# class_nrf52840v2_module.net
KiCad netlist of a schematic drawn in EAGLE
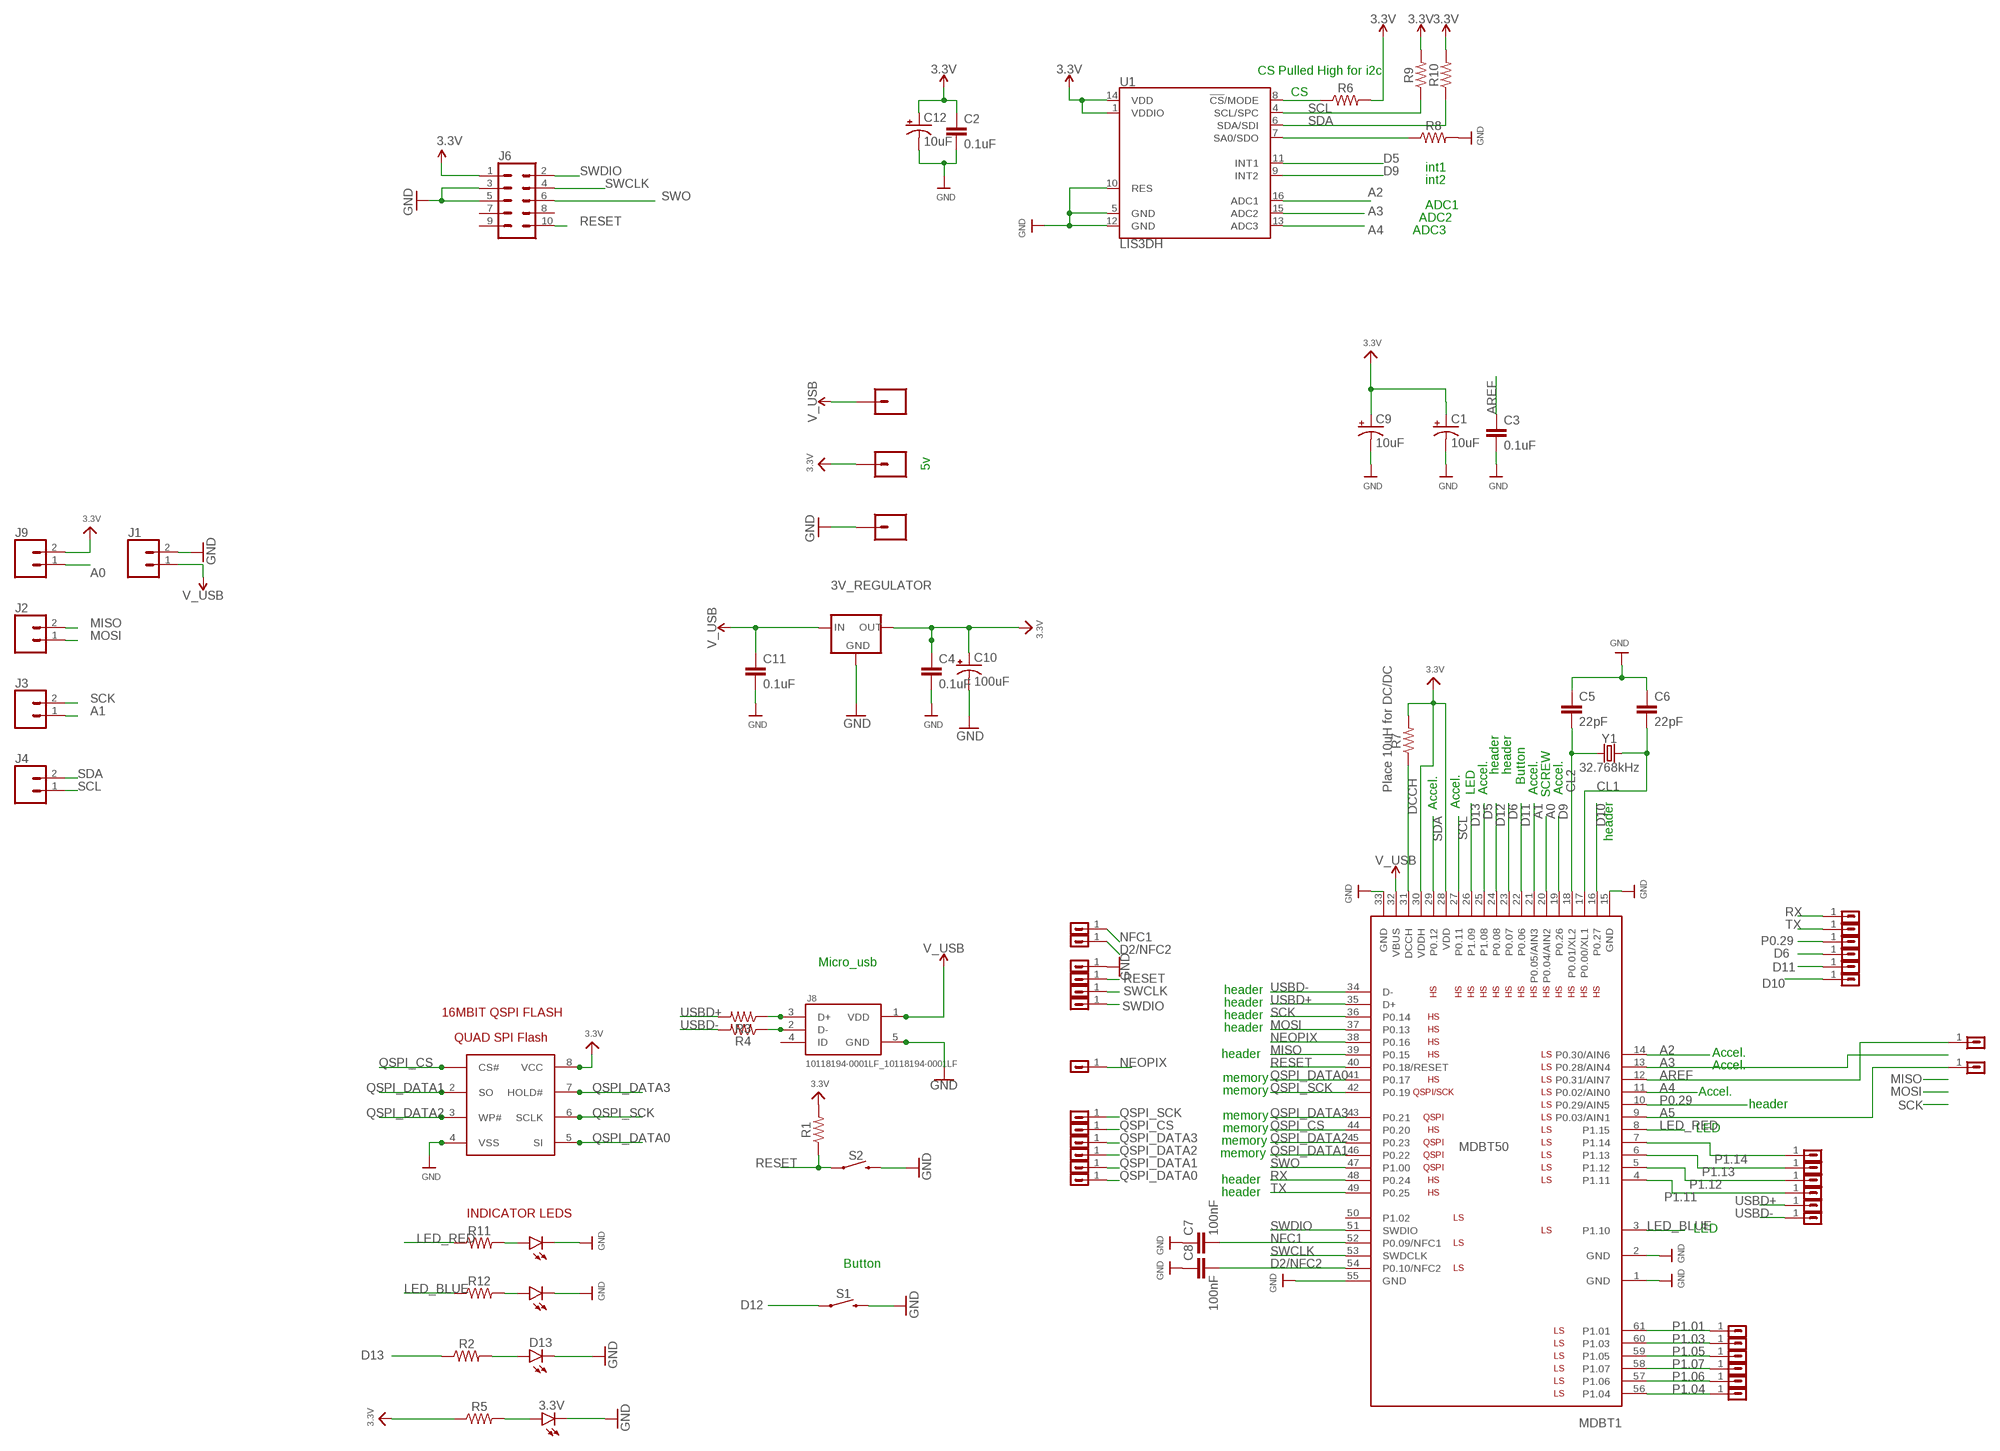
[diagram p0: schematic, sheet 1]

(export (version "E")
  (design (tool "Eeschema 10.0.6"))
  (components
    (comp (ref "3.3V")
      (value "LED5MM-KIT")
      (footprint "eagle-import:LED5MM-KIT")
      (libsource (lib "eagle-import") (part "LED5MM-KIT"))
    )
    (comp (ref "3V_REGULATOR")
      (value "LDL1117_5V_REG")
      (footprint "eagle-import:SOT223")
      (libsource (lib "eagle-import") (part "LDL1117_5V_REG"))
    )
    (comp (ref "C1")
      (value "10uF")
      (footprint "eagle-import:CPOL-RADIAL-2.5MM-5MM-KIT")
      (libsource (lib "eagle-import") (part "10UF-POLAR-RADIAL-2.5MM-KIT-25V-20%"))
    )
    (comp (ref "C2")
      (value "0.1uF")
      (footprint "eagle-import:CAP-PTH-SMALL-KIT")
      (libsource (lib "eagle-import") (part "0.1UF-KIT-EZ-50V-20%"))
    )
    (comp (ref "C3")
      (value "0.1uF")
      (footprint "eagle-import:CAP-PTH-SMALL-KIT")
      (libsource (lib "eagle-import") (part "0.1UF-KIT-EZ-50V-20%"))
    )
    (comp (ref "C4")
      (value "0.1uF")
      (footprint "eagle-import:CAP-PTH-SMALL-KIT")
      (libsource (lib "eagle-import") (part "0.1UF-KIT-EZ-50V-20%"))
    )
    (comp (ref "C5")
      (value "22pF")
      (footprint "eagle-import:CAP-PTH-SMALL-KIT")
      (libsource (lib "eagle-import") (part "0.1UF-KIT-EZ-50V-20%"))
    )
    (comp (ref "C6")
      (value "22pF")
      (footprint "eagle-import:CAP-PTH-SMALL-KIT")
      (libsource (lib "eagle-import") (part "0.1UF-KIT-EZ-50V-20%"))
    )
    (comp (ref "C7")
      (value "100nF")
      (footprint "eagle-import:0805")
      (libsource (lib "eagle-import") (part "10UF-0805-10V-10%"))
    )
    (comp (ref "C8")
      (value "100nF")
      (footprint "eagle-import:0805")
      (libsource (lib "eagle-import") (part "10UF-0805-10V-10%"))
    )
    (comp (ref "C9")
      (value "10uF")
      (footprint "eagle-import:CPOL-RADIAL-2.5MM-5MM-KIT")
      (libsource (lib "eagle-import") (part "10UF-POLAR-RADIAL-2.5MM-KIT-25V-20%"))
    )
    (comp (ref "C10")
      (value "100uF")
      (footprint "eagle-import:CPOL-RADIAL-2.5MM-6.5MM")
      (libsource (lib "eagle-import") (part "100UF-POLAR-RADIAL-2.5MM-25V-20%"))
    )
    (comp (ref "C11")
      (value "0.1uF")
      (footprint "eagle-import:CAP-PTH-SMALL-KIT")
      (libsource (lib "eagle-import") (part "0.1UF-KIT-EZ-50V-20%"))
    )
    (comp (ref "C12")
      (value "10uF")
      (footprint "eagle-import:CPOL-RADIAL-2.5MM-5MM-KIT")
      (libsource (lib "eagle-import") (part "10UF-POLAR-RADIAL-2.5MM-KIT-25V-20%"))
    )
    (comp (ref "D2")
      (value "LED5MM-KIT")
      (footprint "eagle-import:LED5MM-KIT")
      (libsource (lib "eagle-import") (part "LED5MM-KIT"))
    )
    (comp (ref "D3")
      (value "LED5MM-KIT")
      (footprint "eagle-import:LED5MM-KIT")
      (libsource (lib "eagle-import") (part "LED5MM-KIT"))
    )
    (comp (ref "D13")
      (value "LED5MM-KIT")
      (footprint "eagle-import:LED5MM-KIT")
      (libsource (lib "eagle-import") (part "LED5MM-KIT"))
    )
    (comp (ref "J1")
      (value "CONN_025MM")
      (footprint "eagle-import:SCREWTERMINAL-5MM-2")
      (libsource (lib "eagle-import") (part "CONN_025MM"))
    )
    (comp (ref "J2")
      (value "CONN_025MM")
      (footprint "eagle-import:SCREWTERMINAL-5MM-2")
      (libsource (lib "eagle-import") (part "CONN_025MM"))
    )
    (comp (ref "J3")
      (value "CONN_025MM")
      (footprint "eagle-import:SCREWTERMINAL-5MM-2")
      (libsource (lib "eagle-import") (part "CONN_025MM"))
    )
    (comp (ref "J4")
      (value "CONN_025MM")
      (footprint "eagle-import:SCREWTERMINAL-5MM-2")
      (libsource (lib "eagle-import") (part "CONN_025MM"))
    )
    (comp (ref "J5")
      (value "M01PTH")
      (footprint "eagle-import:1X01")
      (libsource (lib "eagle-import") (part "M01PTH"))
    )
    (comp (ref "J6")
      (value "CONN_05X2SHD_SMD")
      (footprint "eagle-import:2X5-SHROUDED_SMD")
      (libsource (lib "eagle-import") (part "CONN_05X2SHD_SMD"))
    )
    (comp (ref "J7")
      (value "M01PTH")
      (footprint "eagle-import:1X01")
      (libsource (lib "eagle-import") (part "M01PTH"))
    )
    (comp (ref "J8")
      (value "10118194-0001LF_10118194-0001LF")
      (footprint "eagle-import:10118194-0001LF_FRAMATOME_10118194-0001LF")
      (fields (field (name "MF") "Amphenol ICC") (field (name "MP") "10118194-0001LF"))
      (libsource (lib "eagle-import") (part "10118194-0001LF_10118194-0001LF"))
    )
    (comp (ref "J9")
      (value "CONN_025MM")
      (footprint "eagle-import:SCREWTERMINAL-5MM-2")
      (libsource (lib "eagle-import") (part "CONN_025MM"))
    )
    (comp (ref "J17")
      (value "M01PTH")
      (footprint "eagle-import:1X01")
      (libsource (lib "eagle-import") (part "M01PTH"))
    )
    (comp (ref "MDBT1")
      (value "MDBT50")
      (footprint "eagle-import:MDBT50")
      (libsource (lib "eagle-import") (part "MDBT50"))
    )
    (comp (ref "R1")
      (value "RESISTORAXIAL-0.3")
      (footprint "eagle-import:AXIAL-0.3")
      (libsource (lib "eagle-import") (part "RESISTORAXIAL-0.3"))
    )
    (comp (ref "R2")
      (value "RESISTORAXIAL-0.3")
      (footprint "eagle-import:AXIAL-0.3")
      (libsource (lib "eagle-import") (part "RESISTORAXIAL-0.3"))
    )
    (comp (ref "R3")
      (value "RESISTOR0805")
      (footprint "eagle-import:0805")
      (libsource (lib "eagle-import") (part "RESISTOR0805"))
    )
    (comp (ref "R4")
      (value "RESISTOR0805")
      (footprint "eagle-import:0805")
      (libsource (lib "eagle-import") (part "RESISTOR0805"))
    )
    (comp (ref "R5")
      (value "RESISTORAXIAL-0.3")
      (footprint "eagle-import:AXIAL-0.3")
      (libsource (lib "eagle-import") (part "RESISTORAXIAL-0.3"))
    )
    (comp (ref "R6")
      (value "RESISTOR0805")
      (footprint "eagle-import:0805")
      (libsource (lib "eagle-import") (part "RESISTOR0805"))
    )
    (comp (ref "R7")
      (value "RESISTORAXIAL-0.3")
      (footprint "eagle-import:AXIAL-0.3")
      (libsource (lib "eagle-import") (part "RESISTORAXIAL-0.3"))
    )
    (comp (ref "R8")
      (value "RESISTOR0805")
      (footprint "eagle-import:0805")
      (libsource (lib "eagle-import") (part "RESISTOR0805"))
    )
    (comp (ref "R9")
      (value "RESISTOR0805")
      (footprint "eagle-import:0805")
      (libsource (lib "eagle-import") (part "RESISTOR0805"))
    )
    (comp (ref "R10")
      (value "RESISTOR0805")
      (footprint "eagle-import:0805")
      (libsource (lib "eagle-import") (part "RESISTOR0805"))
    )
    (comp (ref "R11")
      (value "RESISTORAXIAL-0.3")
      (footprint "eagle-import:AXIAL-0.3")
      (libsource (lib "eagle-import") (part "RESISTORAXIAL-0.3"))
    )
    (comp (ref "R12")
      (value "RESISTORAXIAL-0.3")
      (footprint "eagle-import:AXIAL-0.3")
      (libsource (lib "eagle-import") (part "RESISTORAXIAL-0.3"))
    )
    (comp (ref "S1")
      (value "MOMENTARY-SWITCH-SPST-PTH-12MM")
      (footprint "eagle-import:TACTILE_SWITCH_PTH_12MM")
      (libsource (lib "eagle-import") (part "MOMENTARY-SWITCH-SPST-PTH-12MM"))
    )
    (comp (ref "S2")
      (value "MOMENTARY-SWITCH-SPST-PTH-12MM")
      (footprint "eagle-import:TACTILE_SWITCH_PTH_12MM")
      (libsource (lib "eagle-import") (part "MOMENTARY-SWITCH-SPST-PTH-12MM"))
    )
    (comp (ref "U$4")
      (value "CONN_0138MILL")
      (footprint "eagle-import:1X01-40MILL")
      (libsource (lib "eagle-import") (part "CONN_0138MILL"))
    )
    (comp (ref "U$21")
      (value "CONN_0138MILL")
      (footprint "eagle-import:1X01-40MILL")
      (libsource (lib "eagle-import") (part "CONN_0138MILL"))
    )
    (comp (ref "U$24")
      (value "CONN_0138MILL")
      (footprint "eagle-import:1X01-40MILL")
      (libsource (lib "eagle-import") (part "CONN_0138MILL"))
    )
    (comp (ref "U$26")
      (value "CONN_0138MILL")
      (footprint "eagle-import:1X01-40MILL")
      (libsource (lib "eagle-import") (part "CONN_0138MILL"))
    )
    (comp (ref "U$28")
      (value "CONN_0138MILL")
      (footprint "eagle-import:1X01-40MILL")
      (libsource (lib "eagle-import") (part "CONN_0138MILL"))
    )
    (comp (ref "U$29")
      (value "QUAD_SPI_FLASHSOIC8_300MIL")
      (footprint "eagle-import:SOIC8")
      (libsource (lib "eagle-import") (part "QUAD_SPI_FLASHSOIC8_300MIL"))
    )
    (comp (ref "U$30")
      (value "CONN_0138MILL")
      (footprint "eagle-import:1X01-40MILL")
      (libsource (lib "eagle-import") (part "CONN_0138MILL"))
    )
    (comp (ref "U$31")
      (value "CONN_0138MILL")
      (footprint "eagle-import:1X01-40MILL")
      (libsource (lib "eagle-import") (part "CONN_0138MILL"))
    )
    (comp (ref "U$32")
      (value "CONN_0138MILL")
      (footprint "eagle-import:1X01-40MILL")
      (libsource (lib "eagle-import") (part "CONN_0138MILL"))
    )
    (comp (ref "U$33")
      (value "CONN_0138MILL")
      (footprint "eagle-import:1X01-40MILL")
      (libsource (lib "eagle-import") (part "CONN_0138MILL"))
    )
    (comp (ref "U$34")
      (value "CONN_0138MILL")
      (footprint "eagle-import:1X01-40MILL")
      (libsource (lib "eagle-import") (part "CONN_0138MILL"))
    )
    (comp (ref "U$35")
      (value "CONN_0138MILL")
      (footprint "eagle-import:1X01-40MILL")
      (libsource (lib "eagle-import") (part "CONN_0138MILL"))
    )
    (comp (ref "U$36")
      (value "CONN_0138MILL")
      (footprint "eagle-import:1X01-40MILL")
      (libsource (lib "eagle-import") (part "CONN_0138MILL"))
    )
    (comp (ref "U$37")
      (value "CONN_0138MILL")
      (footprint "eagle-import:1X01-40MILL")
      (libsource (lib "eagle-import") (part "CONN_0138MILL"))
    )
    (comp (ref "U$38")
      (value "CONN_0138MILL")
      (footprint "eagle-import:1X01-40MILL")
      (libsource (lib "eagle-import") (part "CONN_0138MILL"))
    )
    (comp (ref "U$39")
      (value "CONN_0138MILL")
      (footprint "eagle-import:1X01-40MILL")
      (libsource (lib "eagle-import") (part "CONN_0138MILL"))
    )
    (comp (ref "U$40")
      (value "CONN_0138MILL")
      (footprint "eagle-import:1X01-40MILL")
      (libsource (lib "eagle-import") (part "CONN_0138MILL"))
    )
    (comp (ref "U$41")
      (value "CONN_0138MILL")
      (footprint "eagle-import:1X01-40MILL")
      (libsource (lib "eagle-import") (part "CONN_0138MILL"))
    )
    (comp (ref "U$42")
      (value "CONN_0138MILL")
      (footprint "eagle-import:1X01-40MILL")
      (libsource (lib "eagle-import") (part "CONN_0138MILL"))
    )
    (comp (ref "U$43")
      (value "CONN_0138MILL")
      (footprint "eagle-import:1X01-40MILL")
      (libsource (lib "eagle-import") (part "CONN_0138MILL"))
    )
    (comp (ref "U$45")
      (value "CONN_0138MILL")
      (footprint "eagle-import:1X01-40MILL")
      (libsource (lib "eagle-import") (part "CONN_0138MILL"))
    )
    (comp (ref "U$56")
      (value "CONN_0138MILL")
      (footprint "eagle-import:1X01-40MILL")
      (libsource (lib "eagle-import") (part "CONN_0138MILL"))
    )
    (comp (ref "U$57")
      (value "CONN_0138MILL")
      (footprint "eagle-import:1X01-40MILL")
      (libsource (lib "eagle-import") (part "CONN_0138MILL"))
    )
    (comp (ref "U$58")
      (value "CONN_0138MILL")
      (footprint "eagle-import:1X01-40MILL")
      (libsource (lib "eagle-import") (part "CONN_0138MILL"))
    )
    (comp (ref "U$59")
      (value "CONN_0138MILL")
      (footprint "eagle-import:1X01-40MILL")
      (libsource (lib "eagle-import") (part "CONN_0138MILL"))
    )
    (comp (ref "U$60")
      (value "CONN_0138MILL")
      (footprint "eagle-import:1X01-40MILL")
      (libsource (lib "eagle-import") (part "CONN_0138MILL"))
    )
    (comp (ref "U$61")
      (value "CONN_0138MILL")
      (footprint "eagle-import:1X01-40MILL")
      (libsource (lib "eagle-import") (part "CONN_0138MILL"))
    )
    (comp (ref "U$62")
      (value "CONN_0138MILL")
      (footprint "eagle-import:1X01-40MILL")
      (libsource (lib "eagle-import") (part "CONN_0138MILL"))
    )
    (comp (ref "U$63")
      (value "CONN_0138MILL")
      (footprint "eagle-import:1X01-40MILL")
      (libsource (lib "eagle-import") (part "CONN_0138MILL"))
    )
    (comp (ref "U$64")
      (value "CONN_0138MILL")
      (footprint "eagle-import:1X01-40MILL")
      (libsource (lib "eagle-import") (part "CONN_0138MILL"))
    )
    (comp (ref "U$65")
      (value "CONN_0138MILL")
      (footprint "eagle-import:1X01-40MILL")
      (libsource (lib "eagle-import") (part "CONN_0138MILL"))
    )
    (comp (ref "U$66")
      (value "CONN_0138MILL")
      (footprint "eagle-import:1X01-40MILL")
      (libsource (lib "eagle-import") (part "CONN_0138MILL"))
    )
    (comp (ref "U$67")
      (value "CONN_0138MILL")
      (footprint "eagle-import:1X01-40MILL")
      (libsource (lib "eagle-import") (part "CONN_0138MILL"))
    )
    (comp (ref "U$68")
      (value "CONN_0138MILL")
      (footprint "eagle-import:1X01-40MILL")
      (libsource (lib "eagle-import") (part "CONN_0138MILL"))
    )
    (comp (ref "U1")
      (value "LIS3DH")
      (footprint "eagle-import:LGA-16-3X3")
      (libsource (lib "eagle-import") (part "LIS3DH"))
    )
    (comp (ref "Y1")
      (value "32.768kHz")
      (footprint "eagle-import:CRYSTAL-PTH-2X6-CYL")
      (libsource (lib "eagle-import") (part "CRYSTAL-32.768KHZPTH-2X6"))
    )
  )
  (nets
    (net (code "1") (name "/A0") (class "Default")
      (node (ref "J9") (pin "1") (pinfunction "1_1") (pintype "passive"))
      (node (ref "MDBT1") (pin "20") (pinfunction "P0.04/AIN2_20") (pintype "bidirectional"))
    )
    (net (code "2") (name "/A1") (class "Default")
      (node (ref "J3") (pin "1") (pinfunction "1_1") (pintype "passive"))
      (node (ref "MDBT1") (pin "21") (pinfunction "P0.05/AIN3_21") (pintype "bidirectional"))
    )
    (net (code "3") (name "/A2") (class "Default")
      (node (ref "MDBT1") (pin "14") (pinfunction "P0.30/AIN6_14") (pintype "bidirectional"))
      (node (ref "U1") (pin "16") (pinfunction "ADC1_16") (pintype "bidirectional"))
    )
    (net (code "4") (name "/A3") (class "Default")
      (node (ref "MDBT1") (pin "13") (pinfunction "P0.28/AIN4_13") (pintype "bidirectional"))
      (node (ref "U1") (pin "15") (pinfunction "ADC2_15") (pintype "bidirectional"))
    )
    (net (code "5") (name "/A4") (class "Default")
      (node (ref "MDBT1") (pin "11") (pinfunction "P0.02/AIN0_11") (pintype "bidirectional"))
      (node (ref "U1") (pin "13") (pinfunction "ADC3_13") (pintype "bidirectional"))
    )
    (net (code "6") (name "/A5") (class "Default")
      (node (ref "MDBT1") (pin "9") (pinfunction "P0.03/AIN1_9") (pintype "bidirectional"))
      (node (ref "U$45") (pin "1") (pinfunction "1_1") (pintype "passive"))
    )
    (net (code "7") (name "/AREF") (class "Default")
      (node (ref "C3") (pin "1") (pinfunction "1_1") (pintype "passive"))
      (node (ref "MDBT1") (pin "12") (pinfunction "P0.31/AIN7_12") (pintype "bidirectional"))
      (node (ref "U$43") (pin "1") (pinfunction "1_1") (pintype "passive"))
    )
    (net (code "8") (name "/CL1") (class "Default")
      (node (ref "C6") (pin "2") (pinfunction "2_2") (pintype "passive"))
      (node (ref "MDBT1") (pin "17") (pinfunction "P0.00/XL1_17") (pintype "bidirectional"))
      (node (ref "Y1") (pin "2") (pinfunction "2_2") (pintype "passive"))
    )
    (net (code "9") (name "/CL2") (class "Default")
      (node (ref "C5") (pin "2") (pinfunction "2_2") (pintype "passive"))
      (node (ref "MDBT1") (pin "18") (pinfunction "P0.01/XL2_18") (pintype "bidirectional"))
      (node (ref "Y1") (pin "1") (pinfunction "1_1") (pintype "passive"))
    )
    (net (code "10") (name "/D2{slash}NFC2") (class "Default")
      (node (ref "C8") (pin "2") (pinfunction "2_2") (pintype "passive"))
      (node (ref "MDBT1") (pin "54") (pinfunction "P0.10/NFC2_54") (pintype "bidirectional"))
      (node (ref "U$21") (pin "1") (pinfunction "1_1") (pintype "passive"))
    )
    (net (code "11") (name "/D5") (class "Default")
      (node (ref "MDBT1") (pin "25") (pinfunction "P1.08_25") (pintype "bidirectional"))
      (node (ref "U1") (pin "11") (pinfunction "INT1_11") (pintype "bidirectional"))
    )
    (net (code "12") (name "/D6") (class "Default")
      (node (ref "MDBT1") (pin "23") (pinfunction "P0.07_23") (pintype "bidirectional"))
      (node (ref "U$40") (pin "1") (pinfunction "1_1") (pintype "passive"))
    )
    (net (code "13") (name "/D9") (class "Default")
      (node (ref "MDBT1") (pin "19") (pinfunction "P0.26_19") (pintype "bidirectional"))
      (node (ref "U1") (pin "9") (pinfunction "INT2_9") (pintype "bidirectional"))
    )
    (net (code "14") (name "/D10") (class "Default")
      (node (ref "MDBT1") (pin "16") (pinfunction "P0.27_16") (pintype "bidirectional"))
      (node (ref "U$42") (pin "1") (pinfunction "1_1") (pintype "passive"))
    )
    (net (code "15") (name "/D11") (class "Default")
      (node (ref "MDBT1") (pin "22") (pinfunction "P0.06_22") (pintype "bidirectional"))
      (node (ref "U$41") (pin "1") (pinfunction "1_1") (pintype "passive"))
    )
    (net (code "16") (name "/D12") (class "Default")
      (node (ref "MDBT1") (pin "24") (pinfunction "P0.08_24") (pintype "bidirectional"))
      (node (ref "S1") (pin "1") (pinfunction "1_1") (pintype "passive"))
    )
    (net (code "17") (name "/D13") (class "Default")
      (node (ref "MDBT1") (pin "26") (pinfunction "P1.09_26") (pintype "bidirectional"))
      (node (ref "R2") (pin "P$1") (pinfunction "1_P$1") (pintype "passive"))
    )
    (net (code "18") (name "/DCCH") (class "Default")
      (node (ref "MDBT1") (pin "31") (pinfunction "DCCH_31") (pintype "bidirectional"))
      (node (ref "R7") (pin "P$1") (pinfunction "1_P$1") (pintype "passive"))
    )
    (net (code "19") (name "/LED_BLUE") (class "Default")
      (node (ref "MDBT1") (pin "3") (pinfunction "P1.10_3") (pintype "bidirectional"))
      (node (ref "R12") (pin "P$1") (pinfunction "1_P$1") (pintype "passive"))
    )
    (net (code "20") (name "/LED_RED") (class "Default")
      (node (ref "MDBT1") (pin "8") (pinfunction "P1.15_8") (pintype "bidirectional"))
      (node (ref "R11") (pin "P$1") (pinfunction "1_P$1") (pintype "passive"))
    )
    (net (code "21") (name "/MISO") (class "Default")
      (node (ref "J2") (pin "2") (pinfunction "2_2") (pintype "passive"))
      (node (ref "MDBT1") (pin "39") (pinfunction "P0.15_39") (pintype "bidirectional"))
    )
    (net (code "22") (name "/MOSI") (class "Default")
      (node (ref "J2") (pin "1") (pinfunction "1_1") (pintype "passive"))
      (node (ref "MDBT1") (pin "37") (pinfunction "P0.13_37") (pintype "bidirectional"))
    )
    (net (code "23") (name "/NEOPIX") (class "Default")
      (node (ref "MDBT1") (pin "38") (pinfunction "P0.16_38") (pintype "bidirectional"))
      (node (ref "U$68") (pin "1") (pinfunction "1_1") (pintype "passive"))
    )
    (net (code "24") (name "/NFC1") (class "Default")
      (node (ref "C7") (pin "2") (pinfunction "2_2") (pintype "passive"))
      (node (ref "MDBT1") (pin "52") (pinfunction "P0.09/NFC1_52") (pintype "bidirectional"))
      (node (ref "U$4") (pin "1") (pinfunction "1_1") (pintype "passive"))
    )
    (net (code "25") (name "/P0.29") (class "Default")
      (node (ref "MDBT1") (pin "10") (pinfunction "P0.29/AIN5_10") (pintype "bidirectional"))
      (node (ref "U$39") (pin "1") (pinfunction "1_1") (pintype "passive"))
    )
    (net (code "26") (name "/P1.01") (class "Default")
      (node (ref "MDBT1") (pin "61") (pinfunction "P1.01_61") (pintype "bidirectional"))
      (node (ref "U$62") (pin "1") (pinfunction "1_1") (pintype "passive"))
    )
    (net (code "27") (name "/P1.03") (class "Default")
      (node (ref "MDBT1") (pin "60") (pinfunction "P1.03_60") (pintype "bidirectional"))
      (node (ref "U$63") (pin "1") (pinfunction "1_1") (pintype "passive"))
    )
    (net (code "28") (name "/P1.04") (class "Default")
      (node (ref "MDBT1") (pin "56") (pinfunction "P1.04_56") (pintype "bidirectional"))
      (node (ref "U$67") (pin "1") (pinfunction "1_1") (pintype "passive"))
    )
    (net (code "29") (name "/P1.05") (class "Default")
      (node (ref "MDBT1") (pin "59") (pinfunction "P1.05_59") (pintype "bidirectional"))
      (node (ref "U$64") (pin "1") (pinfunction "1_1") (pintype "passive"))
    )
    (net (code "30") (name "/P1.06") (class "Default")
      (node (ref "MDBT1") (pin "57") (pinfunction "P1.06_57") (pintype "bidirectional"))
      (node (ref "U$66") (pin "1") (pinfunction "1_1") (pintype "passive"))
    )
    (net (code "31") (name "/P1.07") (class "Default")
      (node (ref "MDBT1") (pin "58") (pinfunction "P1.07_58") (pintype "bidirectional"))
      (node (ref "U$65") (pin "1") (pinfunction "1_1") (pintype "passive"))
    )
    (net (code "32") (name "/P1.11") (class "Default")
      (node (ref "MDBT1") (pin "4") (pinfunction "P1.11_4") (pintype "bidirectional"))
      (node (ref "U$59") (pin "1") (pinfunction "1_1") (pintype "passive"))
    )
    (net (code "33") (name "/P1.12") (class "Default")
      (node (ref "MDBT1") (pin "5") (pinfunction "P1.12_5") (pintype "bidirectional"))
      (node (ref "U$58") (pin "1") (pinfunction "1_1") (pintype "passive"))
    )
    (net (code "34") (name "/P1.13") (class "Default")
      (node (ref "MDBT1") (pin "6") (pinfunction "P1.13_6") (pintype "bidirectional"))
      (node (ref "U$57") (pin "1") (pinfunction "1_1") (pintype "passive"))
    )
    (net (code "35") (name "/P1.14") (class "Default")
      (node (ref "MDBT1") (pin "7") (pinfunction "P1.14_7") (pintype "bidirectional"))
      (node (ref "U$56") (pin "1") (pinfunction "1_1") (pintype "passive"))
    )
    (net (code "36") (name "/QSPI_CS") (class "Default")
      (node (ref "MDBT1") (pin "44") (pinfunction "P0.20_44") (pintype "bidirectional"))
      (node (ref "U$29") (pin "1") (pinfunction "CS#_1") (pintype "bidirectional"))
      (node (ref "U$32") (pin "1") (pinfunction "1_1") (pintype "passive"))
    )
    (net (code "37") (name "/QSPI_DATA0") (class "Default")
      (node (ref "MDBT1") (pin "41") (pinfunction "P0.17_41") (pintype "bidirectional"))
      (node (ref "U$29") (pin "5") (pinfunction "SI_5") (pintype "bidirectional"))
      (node (ref "U$36") (pin "1") (pinfunction "1_1") (pintype "passive"))
    )
    (net (code "38") (name "/QSPI_DATA1") (class "Default")
      (node (ref "MDBT1") (pin "46") (pinfunction "P0.22_46") (pintype "bidirectional"))
      (node (ref "U$29") (pin "2") (pinfunction "SO_2") (pintype "bidirectional"))
      (node (ref "U$35") (pin "1") (pinfunction "1_1") (pintype "passive"))
    )
    (net (code "39") (name "/QSPI_DATA2") (class "Default")
      (node (ref "MDBT1") (pin "45") (pinfunction "P0.23_45") (pintype "bidirectional"))
      (node (ref "U$29") (pin "3") (pinfunction "WP#_3") (pintype "bidirectional"))
      (node (ref "U$34") (pin "1") (pinfunction "1_1") (pintype "passive"))
    )
    (net (code "40") (name "/QSPI_DATA3") (class "Default")
      (node (ref "MDBT1") (pin "43") (pinfunction "P0.21_43") (pintype "bidirectional"))
      (node (ref "U$29") (pin "7") (pinfunction "HOLD#_7") (pintype "bidirectional"))
      (node (ref "U$33") (pin "1") (pinfunction "1_1") (pintype "passive"))
    )
    (net (code "41") (name "/QSPI_SCK") (class "Default")
      (node (ref "MDBT1") (pin "42") (pinfunction "P0.19_42") (pintype "bidirectional"))
      (node (ref "U$29") (pin "6") (pinfunction "SCLK_6") (pintype "bidirectional"))
      (node (ref "U$31") (pin "1") (pinfunction "1_1") (pintype "passive"))
    )
    (net (code "42") (name "/RESET") (class "Default")
      (node (ref "J6") (pin "10") (pinfunction "10_10") (pintype "passive"))
      (node (ref "MDBT1") (pin "40") (pinfunction "P0.18/RESET_40") (pintype "bidirectional"))
      (node (ref "R1") (pin "P$1") (pinfunction "1_P$1") (pintype "passive"))
      (node (ref "S2") (pin "1") (pinfunction "1_1") (pintype "passive"))
      (node (ref "U$26") (pin "1") (pinfunction "1_1") (pintype "passive"))
    )
    (net (code "43") (name "/RX") (class "Default")
      (node (ref "MDBT1") (pin "48") (pinfunction "P0.24_48") (pintype "bidirectional"))
      (node (ref "U$37") (pin "1") (pinfunction "1_1") (pintype "passive"))
    )
    (net (code "44") (name "/SCK") (class "Default")
      (node (ref "J3") (pin "2") (pinfunction "2_2") (pintype "passive"))
      (node (ref "MDBT1") (pin "36") (pinfunction "P0.14_36") (pintype "bidirectional"))
    )
    (net (code "45") (name "/SCL") (class "Default")
      (node (ref "J4") (pin "1") (pinfunction "1_1") (pintype "passive"))
      (node (ref "MDBT1") (pin "27") (pinfunction "P0.11_27") (pintype "bidirectional"))
      (node (ref "R9") (pin "1") (pinfunction "1_1") (pintype "passive"))
      (node (ref "U1") (pin "4") (pinfunction "SCL/SPC_4") (pintype "bidirectional"))
    )
    (net (code "46") (name "/SDA") (class "Default")
      (node (ref "J4") (pin "2") (pinfunction "2_2") (pintype "passive"))
      (node (ref "MDBT1") (pin "29") (pinfunction "P0.12_29") (pintype "bidirectional"))
      (node (ref "R10") (pin "1") (pinfunction "1_1") (pintype "passive"))
      (node (ref "U1") (pin "6") (pinfunction "SDA/SDI_6") (pintype "bidirectional"))
    )
    (net (code "47") (name "/SWCLK") (class "Default")
      (node (ref "J6") (pin "4") (pinfunction "4_4") (pintype "passive"))
      (node (ref "MDBT1") (pin "53") (pinfunction "SWDCLK_53") (pintype "bidirectional"))
      (node (ref "U$28") (pin "1") (pinfunction "1_1") (pintype "passive"))
    )
    (net (code "48") (name "/SWDIO") (class "Default")
      (node (ref "J6") (pin "2") (pinfunction "2_2") (pintype "passive"))
      (node (ref "MDBT1") (pin "51") (pinfunction "SWDIO_51") (pintype "bidirectional"))
      (node (ref "U$30") (pin "1") (pinfunction "1_1") (pintype "passive"))
    )
    (net (code "49") (name "/SWO") (class "Default")
      (node (ref "J6") (pin "6") (pinfunction "6_6") (pintype "passive"))
      (node (ref "MDBT1") (pin "47") (pinfunction "P1.00_47") (pintype "bidirectional"))
    )
    (net (code "50") (name "/TX") (class "Default")
      (node (ref "MDBT1") (pin "49") (pinfunction "P0.25_49") (pintype "bidirectional"))
      (node (ref "U$38") (pin "1") (pinfunction "1_1") (pintype "passive"))
    )
    (net (code "51") (name "/USBD+") (class "Default")
      (node (ref "MDBT1") (pin "35") (pinfunction "D+_35") (pintype "bidirectional"))
      (node (ref "R3") (pin "2") (pinfunction "2_2") (pintype "passive"))
      (node (ref "U$60") (pin "1") (pinfunction "1_1") (pintype "passive"))
    )
    (net (code "52") (name "/USBD-") (class "Default")
      (node (ref "MDBT1") (pin "34") (pinfunction "D-_34") (pintype "bidirectional"))
      (node (ref "R4") (pin "2") (pinfunction "2_2") (pintype "passive"))
      (node (ref "U$61") (pin "1") (pinfunction "1_1") (pintype "passive"))
    )
    (net (code "53") (name "3.3V") (class "Default")
      (node (ref "3V_REGULATOR") (pin "2") (pinfunction "OUT_2") (pintype "passive"))
      (node (ref "3V_REGULATOR") (pin "4") (pinfunction "OUT_4") (pintype "passive"))
      (node (ref "C1") (pin "1") (pinfunction "+_1") (pintype "passive"))
      (node (ref "C10") (pin "1") (pinfunction "+_1") (pintype "passive"))
      (node (ref "C12") (pin "1") (pinfunction "+_1") (pintype "passive"))
      (node (ref "C2") (pin "1") (pinfunction "1_1") (pintype "passive"))
      (node (ref "C4") (pin "1") (pinfunction "1_1") (pintype "passive"))
      (node (ref "C9") (pin "1") (pinfunction "+_1") (pintype "passive"))
      (node (ref "J17") (pin "1") (pinfunction "1_1") (pintype "passive"))
      (node (ref "J6") (pin "1") (pinfunction "1_1") (pintype "passive"))
      (node (ref "J9") (pin "2") (pinfunction "2_2") (pintype "passive"))
      (node (ref "MDBT1") (pin "28") (pinfunction "VDD_28") (pintype "bidirectional"))
      (node (ref "MDBT1") (pin "30") (pinfunction "VDDH_30") (pintype "bidirectional"))
      (node (ref "R1") (pin "P$2") (pinfunction "2_P$2") (pintype "passive"))
      (node (ref "R10") (pin "2") (pinfunction "2_2") (pintype "passive"))
      (node (ref "R5") (pin "P$1") (pinfunction "1_P$1") (pintype "passive"))
      (node (ref "R6") (pin "2") (pinfunction "2_2") (pintype "passive"))
      (node (ref "R7") (pin "P$2") (pinfunction "2_P$2") (pintype "passive"))
      (node (ref "R9") (pin "2") (pinfunction "2_2") (pintype "passive"))
      (node (ref "U$29") (pin "8") (pinfunction "VCC_8") (pintype "bidirectional"))
      (node (ref "U1") (pin "1") (pinfunction "VDDIO_1") (pintype "bidirectional"))
      (node (ref "U1") (pin "14") (pinfunction "VDD_14") (pintype "bidirectional"))
    )
    (net (code "54") (name "GND") (class "Default")
      (node (ref "3.3V") (pin "K") (pinfunction "C_K") (pintype "passive"))
      (node (ref "3V_REGULATOR") (pin "1") (pinfunction "GND_1") (pintype "input"))
      (node (ref "C1") (pin "2") (pinfunction "-_2") (pintype "passive"))
      (node (ref "C10") (pin "2") (pinfunction "-_2") (pintype "passive"))
      (node (ref "C11") (pin "2") (pinfunction "2_2") (pintype "passive"))
      (node (ref "C12") (pin "2") (pinfunction "-_2") (pintype "passive"))
      (node (ref "C2") (pin "2") (pinfunction "2_2") (pintype "passive"))
      (node (ref "C3") (pin "2") (pinfunction "2_2") (pintype "passive"))
      (node (ref "C4") (pin "2") (pinfunction "2_2") (pintype "passive"))
      (node (ref "C5") (pin "1") (pinfunction "1_1") (pintype "passive"))
      (node (ref "C6") (pin "1") (pinfunction "1_1") (pintype "passive"))
      (node (ref "C7") (pin "1") (pinfunction "1_1") (pintype "passive"))
      (node (ref "C8") (pin "1") (pinfunction "1_1") (pintype "passive"))
      (node (ref "C9") (pin "2") (pinfunction "-_2") (pintype "passive"))
      (node (ref "D13") (pin "K") (pinfunction "C_K") (pintype "passive"))
      (node (ref "D2") (pin "K") (pinfunction "C_K") (pintype "passive"))
      (node (ref "D3") (pin "K") (pinfunction "C_K") (pintype "passive"))
      (node (ref "J1") (pin "2") (pinfunction "2_2") (pintype "passive"))
      (node (ref "J6") (pin "3") (pinfunction "3_3") (pintype "passive"))
      (node (ref "J6") (pin "5") (pinfunction "5_5") (pintype "passive"))
      (node (ref "J7") (pin "1") (pinfunction "1_1") (pintype "passive"))
      (node (ref "J8") (pin "5") (pinfunction "GND_5") (pintype "power_in"))
      (node (ref "MDBT1") (pin "1") (pinfunction "GND_1") (pintype "bidirectional"))
      (node (ref "MDBT1") (pin "15") (pinfunction "GND_15") (pintype "bidirectional"))
      (node (ref "MDBT1") (pin "2") (pinfunction "GND_2") (pintype "bidirectional"))
      (node (ref "MDBT1") (pin "33") (pinfunction "GND_33") (pintype "bidirectional"))
      (node (ref "MDBT1") (pin "55") (pinfunction "GND_55") (pintype "bidirectional"))
      (node (ref "R8") (pin "2") (pinfunction "2_2") (pintype "passive"))
      (node (ref "S1") (pin "3") (pinfunction "2_3") (pintype "passive"))
      (node (ref "S2") (pin "3") (pinfunction "2_3") (pintype "passive"))
      (node (ref "U$24") (pin "1") (pinfunction "1_1") (pintype "passive"))
      (node (ref "U$29") (pin "4") (pinfunction "VSS_4") (pintype "bidirectional"))
      (node (ref "U1") (pin "10") (pinfunction "RES_10") (pintype "bidirectional"))
      (node (ref "U1") (pin "12") (pinfunction "GND_12") (pintype "bidirectional"))
      (node (ref "U1") (pin "5") (pinfunction "GND_5") (pintype "bidirectional"))
    )
    (net (code "55") (name "Net-(J8-D+)") (class "Default")
      (node (ref "J8") (pin "3") (pinfunction "D+_3") (pintype "bidirectional"))
      (node (ref "R3") (pin "1") (pinfunction "1_1") (pintype "passive"))
    )
    (net (code "56") (name "Net-(J8-D-)") (class "Default")
      (node (ref "J8") (pin "2") (pinfunction "D-_2") (pintype "bidirectional"))
      (node (ref "R4") (pin "1") (pinfunction "1_1") (pintype "passive"))
    )
    (net (code "57") (name "Net-(R2-2)") (class "Default")
      (node (ref "D13") (pin "A") (pinfunction "A_A") (pintype "passive"))
      (node (ref "R2") (pin "P$2") (pinfunction "2_P$2") (pintype "passive"))
    )
    (net (code "58") (name "Net-(R5-2)") (class "Default")
      (node (ref "3.3V") (pin "A") (pinfunction "A_A") (pintype "passive"))
      (node (ref "R5") (pin "P$2") (pinfunction "2_P$2") (pintype "passive"))
    )
    (net (code "59") (name "Net-(R11-2)") (class "Default")
      (node (ref "D3") (pin "A") (pinfunction "A_A") (pintype "passive"))
      (node (ref "R11") (pin "P$2") (pinfunction "2_P$2") (pintype "passive"))
    )
    (net (code "60") (name "Net-(R12-2)") (class "Default")
      (node (ref "D2") (pin "A") (pinfunction "A_A") (pintype "passive"))
      (node (ref "R12") (pin "P$2") (pinfunction "2_P$2") (pintype "passive"))
    )
    (net (code "61") (name "Net-(U1-SA0{slash}SDO)") (class "Default")
      (node (ref "R8") (pin "1") (pinfunction "1_1") (pintype "passive"))
      (node (ref "U1") (pin "7") (pinfunction "SA0/SDO_7") (pintype "bidirectional"))
    )
    (net (code "62") (name "Net-(U1-~{CS}{slash}MODE)") (class "Default")
      (node (ref "R6") (pin "1") (pinfunction "1_1") (pintype "passive"))
      (node (ref "U1") (pin "8") (pinfunction "~{CS}/MODE_8") (pintype "bidirectional"))
    )
    (net (code "63") (name "V_USB") (class "Default")
      (node (ref "3V_REGULATOR") (pin "3") (pinfunction "IN_3") (pintype "input"))
      (node (ref "C11") (pin "1") (pinfunction "1_1") (pintype "passive"))
      (node (ref "J1") (pin "1") (pinfunction "1_1") (pintype "passive"))
      (node (ref "J5") (pin "1") (pinfunction "1_1") (pintype "passive"))
      (node (ref "J8") (pin "1") (pinfunction "VDD_1") (pintype "power_in"))
      (node (ref "MDBT1") (pin "32") (pinfunction "VBUS_32") (pintype "bidirectional"))
    )
    (net (code "64") (name "unconnected-(J6-Pad7)") (class "Default")
      (node (ref "J6") (pin "7") (pinfunction "7_7") (pintype "passive"))
    )
    (net (code "65") (name "unconnected-(J6-Pad8)") (class "Default")
      (node (ref "J6") (pin "8") (pinfunction "8_8") (pintype "passive"))
    )
    (net (code "66") (name "unconnected-(J6-Pad9)") (class "Default")
      (node (ref "J6") (pin "9") (pinfunction "9_9") (pintype "passive"))
    )
    (net (code "67") (name "unconnected-(J8-ID-Pad4)") (class "Default")
      (node (ref "J8") (pin "4") (pinfunction "ID_4") (pintype "passive"))
    )
    (net (code "68") (name "unconnected-(MDBT1-P1.02-Pad50)") (class "Default")
      (node (ref "MDBT1") (pin "50") (pinfunction "P1.02_50") (pintype "bidirectional"))
    )
  )
)
